# SCH_V2_0.net
KiCad netlist of a schematic drawn in Altium Designer
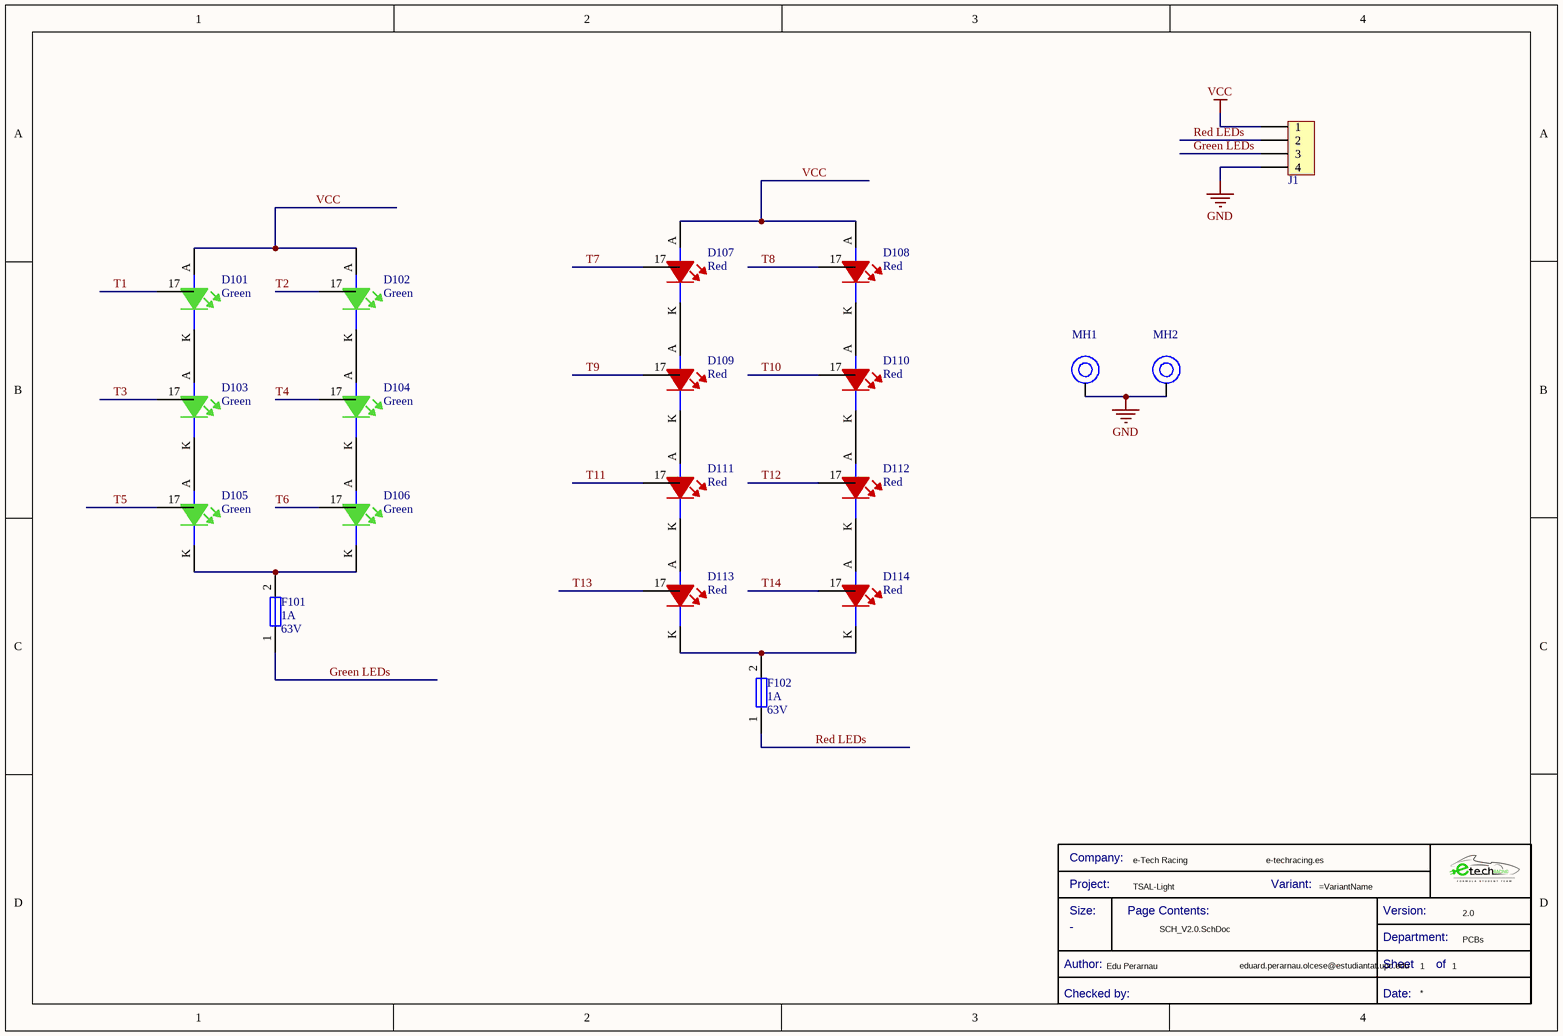
[diagram p0: SCH_V2.0.SchDoc]

(export (version "E")
  (design (tool "Eeschema 10.0.6"))
  (components
    (comp (ref "*")
      (value "Title Block_template")
      (description "Standard Title Block")
      (fields
        (field (name "SIZE") "-")
        (field (name ".CREATOR") "GP")
        (field (name ".PCBCHECK") "GP")
        (field (name ".SCHCHECK") "GP")
      )
      (libsource (lib "e-Tech_Racing") (part "Title Block_template"))
    )
    (comp (ref "D101")
      (value "150353GS74500")
      (footprint "LED_3535_WE - duplicate")
      (description "High Brightness LED, WL-SMDC Series, 525 nm, Green, 85 lm, 350 mA")
      (fields
        (field (name "MANUFACTURER") "Wurth Electronics")
        (field (name "COLOR") "Green")
        (field (name ".CREATOR") "GP")
      )
      (libsource (lib "Semiconductor") (part "LEDGS-3535-85_DUPLICATE"))
    )
    (comp (ref "D102")
      (value "150353GS74500")
      (footprint "LED_3535_WE - duplicate")
      (description "High Brightness LED, WL-SMDC Series, 525 nm, Green, 85 lm, 350 mA")
      (fields
        (field (name "MANUFACTURER") "Wurth Electronics")
        (field (name "COLOR") "Green")
        (field (name ".CREATOR") "GP")
      )
      (libsource (lib "Semiconductor") (part "LEDGS-3535-85_DUPLICATE"))
    )
    (comp (ref "D103")
      (value "150353GS74500")
      (footprint "LED_3535_WE - duplicate")
      (description "High Brightness LED, WL-SMDC Series, 525 nm, Green, 85 lm, 350 mA")
      (fields
        (field (name "MANUFACTURER") "Wurth Electronics")
        (field (name "COLOR") "Green")
        (field (name ".CREATOR") "GP")
      )
      (libsource (lib "Semiconductor") (part "LEDGS-3535-85_DUPLICATE"))
    )
    (comp (ref "D104")
      (value "150353GS74500")
      (footprint "LED_3535_WE - duplicate")
      (description "High Brightness LED, WL-SMDC Series, 525 nm, Green, 85 lm, 350 mA")
      (fields
        (field (name "MANUFACTURER") "Wurth Electronics")
        (field (name "COLOR") "Green")
        (field (name ".CREATOR") "GP")
      )
      (libsource (lib "Semiconductor") (part "LEDGS-3535-85_DUPLICATE"))
    )
    (comp (ref "D105")
      (value "150353GS74500")
      (footprint "LED_3535_WE - duplicate")
      (description "High Brightness LED, WL-SMDC Series, 525 nm, Green, 85 lm, 350 mA")
      (fields
        (field (name "MANUFACTURER") "Wurth Electronics")
        (field (name "COLOR") "Green")
        (field (name ".CREATOR") "GP")
      )
      (libsource (lib "Semiconductor") (part "LEDGS-3535-85_DUPLICATE"))
    )
    (comp (ref "D106")
      (value "150353GS74500")
      (footprint "LED_3535_WE - duplicate")
      (description "High Brightness LED, WL-SMDC Series, 525 nm, Green, 85 lm, 350 mA")
      (fields
        (field (name "MANUFACTURER") "Wurth Electronics")
        (field (name "COLOR") "Green")
        (field (name ".CREATOR") "GP")
      )
      (libsource (lib "Semiconductor") (part "LEDGS-3535-85_DUPLICATE"))
    )
    (comp (ref "D107")
      (value "150353RS74500")
      (footprint "LED_3535_WE - duplicate")
      (description "High Brightness Led, Wl-Smdc Series, 625 Nm, Red, 55 Lm, 350 Ma")
      (fields
        (field (name "MANUFACTURER") "Wurth Electronics")
        (field (name "COLOR") "Red")
        (field (name ".CREATOR") "GP")
      )
      (libsource (lib "Semiconductor") (part "LEDRS-3535-55_DUPLICATE"))
    )
    (comp (ref "D108")
      (value "150353RS74500")
      (footprint "LED_3535_WE - duplicate")
      (description "High Brightness Led, Wl-Smdc Series, 625 Nm, Red, 55 Lm, 350 Ma")
      (fields
        (field (name "MANUFACTURER") "Wurth Electronics")
        (field (name "COLOR") "Red")
        (field (name ".CREATOR") "GP")
      )
      (libsource (lib "Semiconductor") (part "LEDRS-3535-55_DUPLICATE"))
    )
    (comp (ref "D109")
      (value "150353RS74500")
      (footprint "LED_3535_WE - duplicate")
      (description "High Brightness Led, Wl-Smdc Series, 625 Nm, Red, 55 Lm, 350 Ma")
      (fields
        (field (name "MANUFACTURER") "Wurth Electronics")
        (field (name "COLOR") "Red")
        (field (name ".CREATOR") "GP")
      )
      (libsource (lib "Semiconductor") (part "LEDRS-3535-55_DUPLICATE"))
    )
    (comp (ref "D110")
      (value "150353RS74500")
      (footprint "LED_3535_WE - duplicate")
      (description "High Brightness Led, Wl-Smdc Series, 625 Nm, Red, 55 Lm, 350 Ma")
      (fields
        (field (name "MANUFACTURER") "Wurth Electronics")
        (field (name "COLOR") "Red")
        (field (name ".CREATOR") "GP")
      )
      (libsource (lib "Semiconductor") (part "LEDRS-3535-55_DUPLICATE"))
    )
    (comp (ref "D111")
      (value "150353RS74500")
      (footprint "LED_3535_WE - duplicate")
      (description "High Brightness Led, Wl-Smdc Series, 625 Nm, Red, 55 Lm, 350 Ma")
      (fields
        (field (name "MANUFACTURER") "Wurth Electronics")
        (field (name "COLOR") "Red")
        (field (name ".CREATOR") "GP")
      )
      (libsource (lib "Semiconductor") (part "LEDRS-3535-55_DUPLICATE"))
    )
    (comp (ref "D112")
      (value "150353RS74500")
      (footprint "LED_3535_WE - duplicate")
      (description "High Brightness Led, Wl-Smdc Series, 625 Nm, Red, 55 Lm, 350 Ma")
      (fields
        (field (name "MANUFACTURER") "Wurth Electronics")
        (field (name "COLOR") "Red")
        (field (name ".CREATOR") "GP")
      )
      (libsource (lib "Semiconductor") (part "LEDRS-3535-55_DUPLICATE"))
    )
    (comp (ref "D113")
      (value "150353RS74500")
      (footprint "LED_3535_WE - duplicate")
      (description "High Brightness Led, Wl-Smdc Series, 625 Nm, Red, 55 Lm, 350 Ma")
      (fields
        (field (name "MANUFACTURER") "Wurth Electronics")
        (field (name "COLOR") "Red")
        (field (name ".CREATOR") "GP")
      )
      (libsource (lib "Semiconductor") (part "LEDRS-3535-55_DUPLICATE"))
    )
    (comp (ref "D114")
      (value "150353RS74500")
      (footprint "LED_3535_WE - duplicate")
      (description "High Brightness Led, Wl-Smdc Series, 625 Nm, Red, 55 Lm, 350 Ma")
      (fields
        (field (name "MANUFACTURER") "Wurth Electronics")
        (field (name "COLOR") "Red")
        (field (name ".CREATOR") "GP")
      )
      (libsource (lib "Semiconductor") (part "LEDRS-3535-55_DUPLICATE"))
    )
    (comp (ref "F101")
      (value "0437001.WRA")
      (footprint "Fuse_1206")
      (description "Fuse Chip Fast Acting 1A 63V SMD Solder Pad 1206 Ceramic T/R Automotive")
      (fields
        (field (name "MANUFACTURER") "Littelfuse")
        (field (name "CURRENT RATING") "1A")
        (field (name "VOLTAGE RATING (DC)") "63V")
        (field (name ".CREATOR") "DO")
      )
      (libsource (lib "Filter components") (part "Fuse_1A_63V_1206"))
    )
    (comp (ref "F102")
      (value "0437001.WRA")
      (footprint "Fuse_1206")
      (description "Fuse Chip Fast Acting 1A 63V SMD Solder Pad 1206 Ceramic T/R Automotive")
      (fields
        (field (name "MANUFACTURER") "Littelfuse")
        (field (name "CURRENT RATING") "1A")
        (field (name "VOLTAGE RATING (DC)") "63V")
        (field (name ".CREATOR") "DO")
      )
      (libsource (lib "Filter components") (part "Fuse_1A_63V_1206"))
    )
    (comp (ref "J1")
      (value "436500400")
      (footprint "J_MicroFit_1x4")
      (description "Connector Wire to Board Header 4 Position 3mm Solder Right Angle Thru-Hole Tray")
      (libsource (lib "Electromechanical") (part "J_MicroFit_1x4"))
    )
    (comp (ref "MH1")
      (value "Mounting_Hole_M3")
      (footprint "Mounting_Hole_M3")
      (libsource (lib "Electromechanical") (part "Mounting_Hole_M3"))
    )
    (comp (ref "MH2")
      (value "Mounting_Hole_M3")
      (footprint "Mounting_Hole_M3")
      (libsource (lib "Electromechanical") (part "Mounting_Hole_M3"))
    )
  )
  (nets
    (net (code "1") (name "/Green LEDs") (class "Default")
      (node (ref "F101") (pin "1") (pinfunction "1_1") (pintype "passive"))
      (node (ref "J1") (pin "3") (pinfunction "3_3") (pintype "passive"))
    )
    (net (code "2") (name "/Red LEDs") (class "Default")
      (node (ref "F102") (pin "1") (pinfunction "1_1") (pintype "passive"))
      (node (ref "J1") (pin "2") (pinfunction "2_2") (pintype "passive"))
    )
    (net (code "3") (name "/T1") (class "Default")
      (node (ref "D101") (pin "17") (pinfunction "17_17") (pintype "passive"))
    )
    (net (code "4") (name "/T2") (class "Default")
      (node (ref "D102") (pin "17") (pinfunction "17_17") (pintype "passive"))
    )
    (net (code "5") (name "/T3") (class "Default")
      (node (ref "D103") (pin "17") (pinfunction "17_17") (pintype "passive"))
    )
    (net (code "6") (name "/T4") (class "Default")
      (node (ref "D104") (pin "17") (pinfunction "17_17") (pintype "passive"))
    )
    (net (code "7") (name "/T5") (class "Default")
      (node (ref "D105") (pin "17") (pinfunction "17_17") (pintype "passive"))
    )
    (net (code "8") (name "/T6") (class "Default")
      (node (ref "D106") (pin "17") (pinfunction "17_17") (pintype "passive"))
    )
    (net (code "9") (name "/T7") (class "Default")
      (node (ref "D107") (pin "17") (pinfunction "17_17") (pintype "passive"))
    )
    (net (code "10") (name "/T8") (class "Default")
      (node (ref "D108") (pin "17") (pinfunction "17_17") (pintype "passive"))
    )
    (net (code "11") (name "/T9") (class "Default")
      (node (ref "D109") (pin "17") (pinfunction "17_17") (pintype "passive"))
    )
    (net (code "12") (name "/T10") (class "Default")
      (node (ref "D110") (pin "17") (pinfunction "17_17") (pintype "passive"))
    )
    (net (code "13") (name "/T11") (class "Default")
      (node (ref "D111") (pin "17") (pinfunction "17_17") (pintype "passive"))
    )
    (net (code "14") (name "/T12") (class "Default")
      (node (ref "D112") (pin "17") (pinfunction "17_17") (pintype "passive"))
    )
    (net (code "15") (name "/T13") (class "Default")
      (node (ref "D113") (pin "17") (pinfunction "17_17") (pintype "passive"))
    )
    (net (code "16") (name "/T14") (class "Default")
      (node (ref "D114") (pin "17") (pinfunction "17_17") (pintype "passive"))
    )
    (net (code "17") (name "GND") (class "Default")
      (node (ref "J1") (pin "4") (pinfunction "4_4") (pintype "passive"))
      (node (ref "MH1") (pin "1") (pinfunction "1_1") (pintype "passive"))
      (node (ref "MH2") (pin "1") (pinfunction "1_1") (pintype "passive"))
    )
    (net (code "18") (name "Net-(D101-PadK)") (class "Default")
      (node (ref "D101") (pin "K") (pinfunction "K_K") (pintype "passive"))
      (node (ref "D103") (pin "A") (pinfunction "A_A") (pintype "passive"))
    )
    (net (code "19") (name "Net-(D102-PadK)") (class "Default")
      (node (ref "D102") (pin "K") (pinfunction "K_K") (pintype "passive"))
      (node (ref "D104") (pin "A") (pinfunction "A_A") (pintype "passive"))
    )
    (net (code "20") (name "Net-(D103-PadK)") (class "Default")
      (node (ref "D103") (pin "K") (pinfunction "K_K") (pintype "passive"))
      (node (ref "D105") (pin "A") (pinfunction "A_A") (pintype "passive"))
    )
    (net (code "21") (name "Net-(D104-PadK)") (class "Default")
      (node (ref "D104") (pin "K") (pinfunction "K_K") (pintype "passive"))
      (node (ref "D106") (pin "A") (pinfunction "A_A") (pintype "passive"))
    )
    (net (code "22") (name "Net-(D105-PadK)") (class "Default")
      (node (ref "D105") (pin "K") (pinfunction "K_K") (pintype "passive"))
      (node (ref "D106") (pin "K") (pinfunction "K_K") (pintype "passive"))
      (node (ref "F101") (pin "2") (pinfunction "2_2") (pintype "passive"))
    )
    (net (code "23") (name "Net-(D107-PadK)") (class "Default")
      (node (ref "D107") (pin "K") (pinfunction "K_K") (pintype "passive"))
      (node (ref "D109") (pin "A") (pinfunction "A_A") (pintype "passive"))
    )
    (net (code "24") (name "Net-(D108-PadK)") (class "Default")
      (node (ref "D108") (pin "K") (pinfunction "K_K") (pintype "passive"))
      (node (ref "D110") (pin "A") (pinfunction "A_A") (pintype "passive"))
    )
    (net (code "25") (name "Net-(D109-PadK)") (class "Default")
      (node (ref "D109") (pin "K") (pinfunction "K_K") (pintype "passive"))
      (node (ref "D111") (pin "A") (pinfunction "A_A") (pintype "passive"))
    )
    (net (code "26") (name "Net-(D110-PadK)") (class "Default")
      (node (ref "D110") (pin "K") (pinfunction "K_K") (pintype "passive"))
      (node (ref "D112") (pin "A") (pinfunction "A_A") (pintype "passive"))
    )
    (net (code "27") (name "Net-(D111-PadK)") (class "Default")
      (node (ref "D111") (pin "K") (pinfunction "K_K") (pintype "passive"))
      (node (ref "D113") (pin "A") (pinfunction "A_A") (pintype "passive"))
    )
    (net (code "28") (name "Net-(D112-PadK)") (class "Default")
      (node (ref "D112") (pin "K") (pinfunction "K_K") (pintype "passive"))
      (node (ref "D114") (pin "A") (pinfunction "A_A") (pintype "passive"))
    )
    (net (code "29") (name "Net-(D113-PadK)") (class "Default")
      (node (ref "D113") (pin "K") (pinfunction "K_K") (pintype "passive"))
      (node (ref "D114") (pin "K") (pinfunction "K_K") (pintype "passive"))
      (node (ref "F102") (pin "2") (pinfunction "2_2") (pintype "passive"))
    )
    (net (code "30") (name "VCC") (class "Default")
      (node (ref "D101") (pin "A") (pinfunction "A_A") (pintype "passive"))
      (node (ref "D102") (pin "A") (pinfunction "A_A") (pintype "passive"))
      (node (ref "D107") (pin "A") (pinfunction "A_A") (pintype "passive"))
      (node (ref "D108") (pin "A") (pinfunction "A_A") (pintype "passive"))
      (node (ref "J1") (pin "1") (pinfunction "1_1") (pintype "passive"))
    )
  )
)
